# Lichtschranke.net
KiCad netlist of a schematic drawn in EAGLE
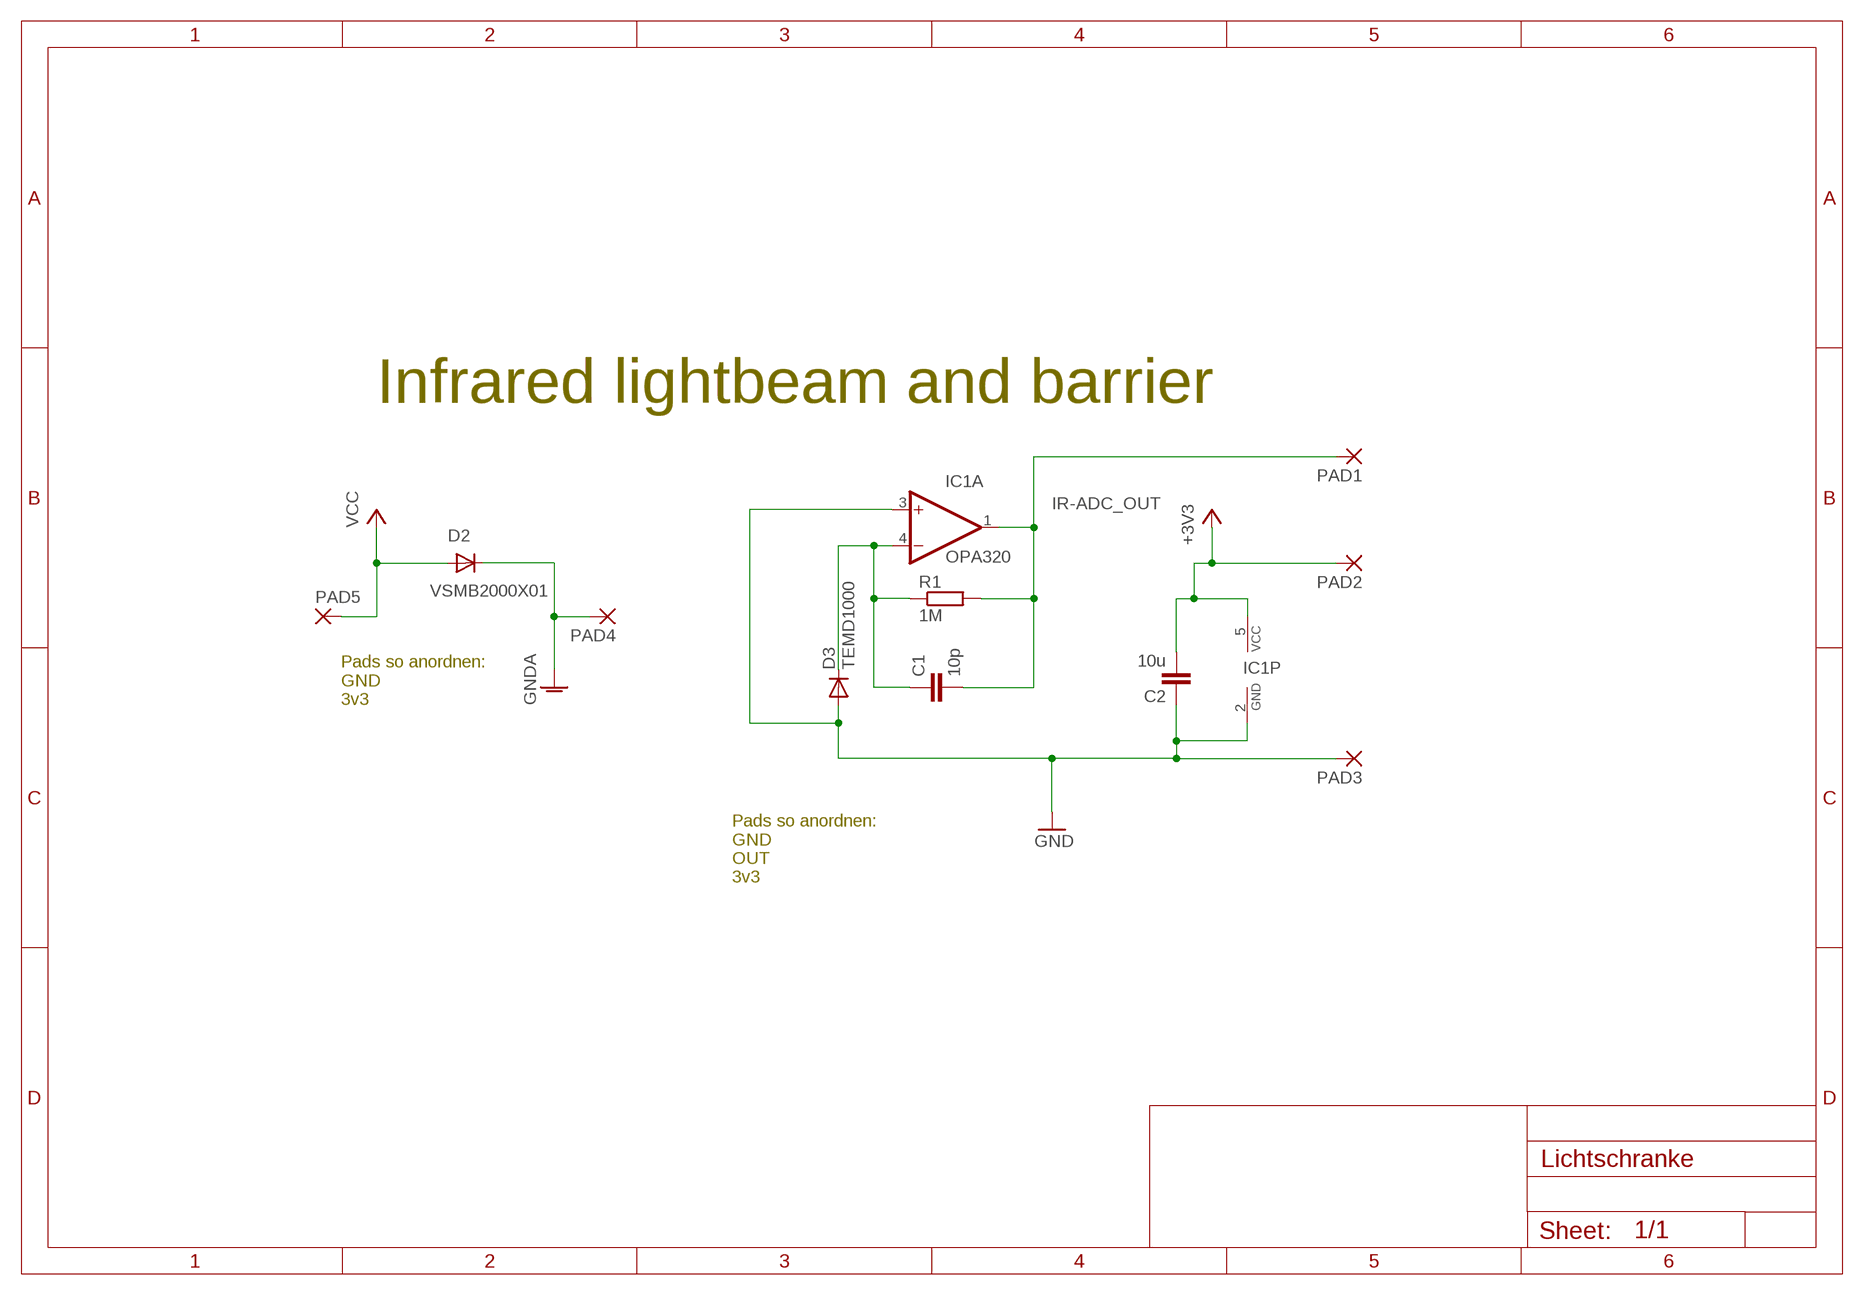
[diagram p0: schematic, sheet 1]

(export (version "E")
  (design (tool "Eeschema 10.0.6"))
  (components
    (comp (ref "C1")
      (value "10p")
      (footprint "eagle-import:C0603")
      (libsource (lib "eagle-import") (part "C-EUC0603"))
    )
    (comp (ref "C2")
      (value "10u")
      (footprint "eagle-import:C0603")
      (libsource (lib "eagle-import") (part "C-EUC0603"))
    )
    (comp (ref "D2")
      (value "VSMB2000X01")
      (footprint "eagle-import:LED-GULLR")
      (libsource (lib "eagle-import") (part "DIODE"))
    )
    (comp (ref "D3")
      (value "TEMD1000")
      (footprint "eagle-import:LED-GULLR")
      (libsource (lib "eagle-import") (part "DIODE"))
    )
    (comp (ref "IC1")
      (value "OPA320")
      (footprint "eagle-import:SOT23-5")
      (libsource (lib "eagle-import") (part "AD-OP1RT"))
    )
    (comp (ref "PAD1")
      (value "SMD2")
      (footprint "eagle-import:SMD1,27-2,54")
      (libsource (lib "eagle-import") (part "SMD2"))
    )
    (comp (ref "PAD2")
      (value "SMD2")
      (footprint "eagle-import:SMD1,27-2,54")
      (libsource (lib "eagle-import") (part "SMD2"))
    )
    (comp (ref "PAD3")
      (value "SMD2")
      (footprint "eagle-import:SMD1,27-2,54")
      (libsource (lib "eagle-import") (part "SMD2"))
    )
    (comp (ref "PAD4")
      (value "SMD2")
      (footprint "eagle-import:SMD1,27-2,54")
      (libsource (lib "eagle-import") (part "SMD2"))
    )
    (comp (ref "PAD5")
      (value "SMD2")
      (footprint "eagle-import:SMD1,27-2,54")
      (libsource (lib "eagle-import") (part "SMD2"))
    )
    (comp (ref "R1")
      (value "1M")
      (footprint "eagle-import:R0603")
      (libsource (lib "eagle-import") (part "R-EU_R0603"))
    )
  )
  (nets
    (net (code "1") (name "+3V3") (class "Default")
      (node (ref "C2") (pin "2") (pinfunction "2_2") (pintype "passive"))
      (node (ref "IC1") (pin "5") (pinfunction "VCC_5") (pintype "power_in"))
      (node (ref "PAD2") (pin "1") (pinfunction "P_1") (pintype "passive"))
    )
    (net (code "2") (name "/IR-ADC_OUT") (class "Default")
      (node (ref "C1") (pin "2") (pinfunction "2_2") (pintype "passive"))
      (node (ref "IC1") (pin "1") (pinfunction "OUT_1") (pintype "output"))
      (node (ref "PAD1") (pin "1") (pinfunction "P_1") (pintype "passive"))
      (node (ref "R1") (pin "2") (pinfunction "2_2") (pintype "passive"))
    )
    (net (code "3") (name "GND") (class "Default")
      (node (ref "C2") (pin "1") (pinfunction "1_1") (pintype "passive"))
      (node (ref "D3") (pin "A") (pinfunction "A_A") (pintype "passive"))
      (node (ref "IC1") (pin "2") (pinfunction "GND_2") (pintype "power_in"))
      (node (ref "IC1") (pin "3") (pinfunction "+IN_3") (pintype "input"))
      (node (ref "PAD3") (pin "1") (pinfunction "P_1") (pintype "passive"))
    )
    (net (code "4") (name "GNDA") (class "Default")
      (node (ref "D2") (pin "C") (pinfunction "C_C") (pintype "passive"))
      (node (ref "PAD4") (pin "1") (pinfunction "P_1") (pintype "passive"))
    )
    (net (code "5") (name "Net-(IC1A--IN)") (class "Default")
      (node (ref "C1") (pin "1") (pinfunction "1_1") (pintype "passive"))
      (node (ref "D3") (pin "C") (pinfunction "C_C") (pintype "passive"))
      (node (ref "IC1") (pin "4") (pinfunction "-IN_4") (pintype "input"))
      (node (ref "R1") (pin "1") (pinfunction "1_1") (pintype "passive"))
    )
    (net (code "6") (name "VCC") (class "Default")
      (node (ref "D2") (pin "A") (pinfunction "A_A") (pintype "passive"))
      (node (ref "PAD5") (pin "1") (pinfunction "P_1") (pintype "passive"))
    )
  )
)
